# version_1_1.net
KiCad netlist of a schematic drawn in EAGLE
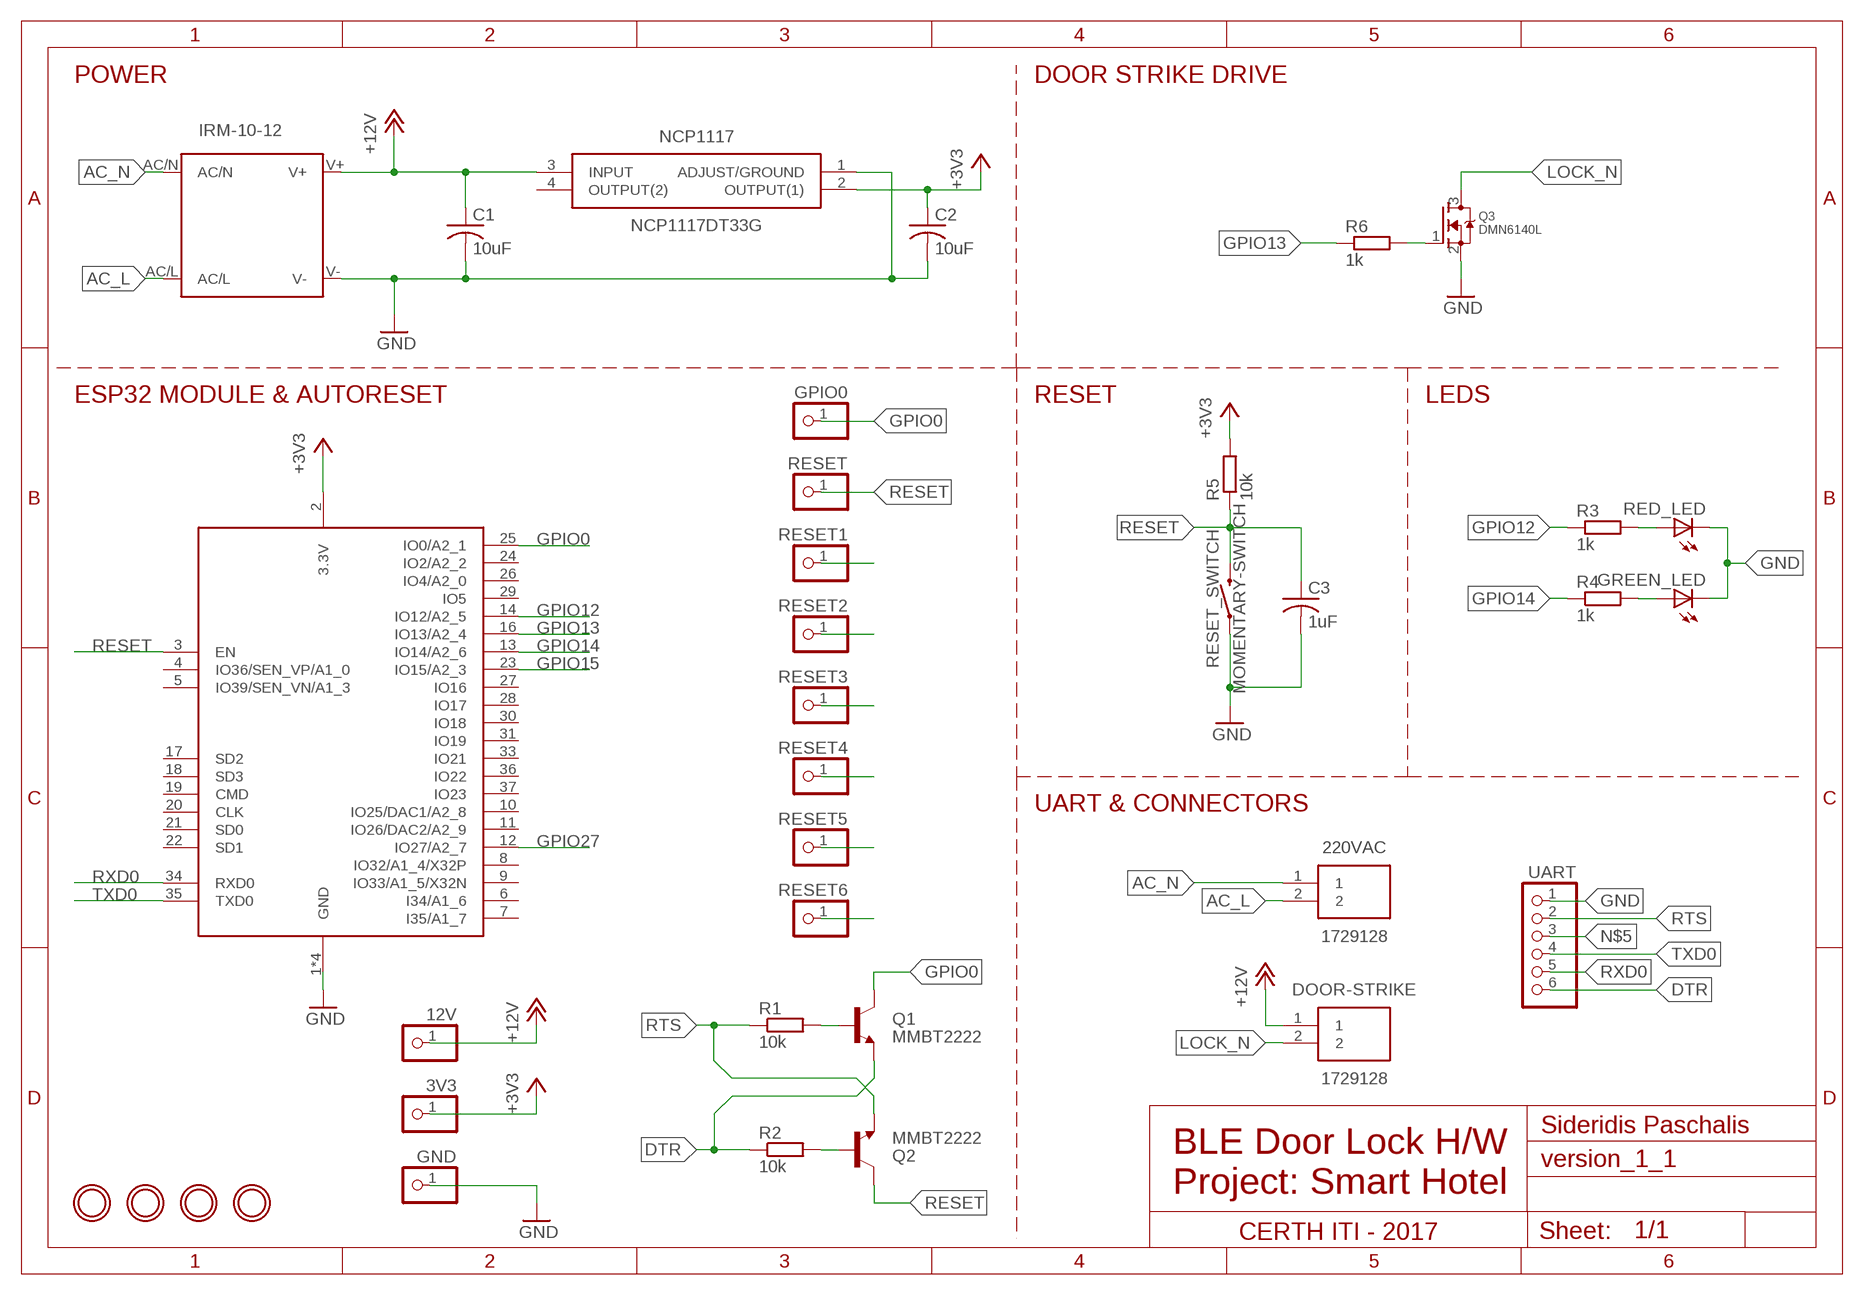
[diagram p0: schematic, sheet 1]

(export (version "E")
  (design (tool "Eeschema 10.0.6"))
  (components
    (comp (ref "3V3")
      (value "PINHD-1X1")
      (footprint "eagle-import:1X01")
      (libsource (lib "eagle-import") (part "PINHD-1X1"))
    )
    (comp (ref "12V")
      (value "PINHD-1X1")
      (footprint "eagle-import:1X01")
      (libsource (lib "eagle-import") (part "PINHD-1X1"))
    )
    (comp (ref "220VAC")
      (value "1729128")
      (footprint "eagle-import:HDRV2W110P0X508_1X2_1016X810X1")
      (fields (field (name "RS_PART_NUMBER") "1930586"))
      (libsource (lib "eagle-import") (part "1729128"))
    )
    (comp (ref "C1")
      (value "10uF")
      (footprint "eagle-import:C0805")
      (libsource (lib "eagle-import") (part "C-USC0805"))
    )
    (comp (ref "C2")
      (value "10uF")
      (footprint "eagle-import:C0805")
      (libsource (lib "eagle-import") (part "C-USC0805"))
    )
    (comp (ref "C3")
      (value "1uF")
      (footprint "eagle-import:C0805")
      (libsource (lib "eagle-import") (part "C-USC0805"))
    )
    (comp (ref "DOOR-STRIKE")
      (value "1729128")
      (footprint "eagle-import:HDRV2W110P0X508_1X2_1016X810X1")
      (fields (field (name "RS_PART_NUMBER") "1930586"))
      (libsource (lib "eagle-import") (part "1729128"))
    )
    (comp (ref "ESP32")
      (value "ESP32_WROOM32_SKINNY")
      (footprint "eagle-import:WROOM32_SKINNY")
      (libsource (lib "eagle-import") (part "ESP32_WROOM32_SKINNY"))
    )
    (comp (ref "GND")
      (value "PINHD-1X1")
      (footprint "eagle-import:1X01")
      (libsource (lib "eagle-import") (part "PINHD-1X1"))
    )
    (comp (ref "GPIO0")
      (value "PINHD-1X1")
      (footprint "eagle-import:1X01")
      (libsource (lib "eagle-import") (part "PINHD-1X1"))
    )
    (comp (ref "GREEN_LED")
      (value "LED5MM")
      (footprint "eagle-import:LED5MM")
      (libsource (lib "eagle-import") (part "LED5MM"))
    )
    (comp (ref "IRM-10-12")
      (value "IRM_05/10")
      (footprint "eagle-import:IRM_05_10")
      (libsource (lib "eagle-import") (part "IRM_05/10"))
    )
    (comp (ref "NCP1117")
      (value "NCP1117DT33G")
      (footprint "eagle-import:TO229P990X238-4N")
      (fields (field (name "RS_PART_NUMBER") "1023504"))
      (libsource (lib "eagle-import") (part "NCP1117DT33G"))
    )
    (comp (ref "Q1")
      (value "MMBT2222")
      (footprint "eagle-import:SOT23")
      (libsource (lib "eagle-import") (part "TRANSISTOR_NPNSOT23"))
    )
    (comp (ref "Q2")
      (value "MMBT2222")
      (footprint "eagle-import:SOT23")
      (libsource (lib "eagle-import") (part "TRANSISTOR_NPNSOT23"))
    )
    (comp (ref "Q3")
      (value "DMN6140L")
      (footprint "eagle-import:SOT23")
      (libsource (lib "eagle-import") (part "MOSFET-NREFLOW"))
    )
    (comp (ref "R1")
      (value "10k")
      (footprint "eagle-import:R0805")
      (libsource (lib "eagle-import") (part "R-EU_R0805"))
    )
    (comp (ref "R2")
      (value "10k")
      (footprint "eagle-import:R0805")
      (libsource (lib "eagle-import") (part "R-EU_R0805"))
    )
    (comp (ref "R3")
      (value "1k")
      (footprint "eagle-import:R0805")
      (libsource (lib "eagle-import") (part "R-EU_R0805"))
    )
    (comp (ref "R4")
      (value "1k")
      (footprint "eagle-import:R0805")
      (libsource (lib "eagle-import") (part "R-EU_R0805"))
    )
    (comp (ref "R5")
      (value "10k")
      (footprint "eagle-import:R0805")
      (libsource (lib "eagle-import") (part "R-EU_R0805"))
    )
    (comp (ref "R6")
      (value "1k")
      (footprint "eagle-import:R0805")
      (libsource (lib "eagle-import") (part "R-EU_R0805"))
    )
    (comp (ref "RED_LED")
      (value "LED5MM")
      (footprint "eagle-import:LED5MM")
      (libsource (lib "eagle-import") (part "LED5MM"))
    )
    (comp (ref "RESET")
      (value "PINHD-1X1")
      (footprint "eagle-import:1X01")
      (libsource (lib "eagle-import") (part "PINHD-1X1"))
    )
    (comp (ref "RESET1")
      (value "PINHD-1X1")
      (footprint "eagle-import:1X01")
      (libsource (lib "eagle-import") (part "PINHD-1X1"))
    )
    (comp (ref "RESET2")
      (value "PINHD-1X1")
      (footprint "eagle-import:1X01")
      (libsource (lib "eagle-import") (part "PINHD-1X1"))
    )
    (comp (ref "RESET3")
      (value "PINHD-1X1")
      (footprint "eagle-import:1X01")
      (libsource (lib "eagle-import") (part "PINHD-1X1"))
    )
    (comp (ref "RESET4")
      (value "PINHD-1X1")
      (footprint "eagle-import:1X01")
      (libsource (lib "eagle-import") (part "PINHD-1X1"))
    )
    (comp (ref "RESET5")
      (value "PINHD-1X1")
      (footprint "eagle-import:1X01")
      (libsource (lib "eagle-import") (part "PINHD-1X1"))
    )
    (comp (ref "RESET6")
      (value "PINHD-1X1")
      (footprint "eagle-import:1X01")
      (libsource (lib "eagle-import") (part "PINHD-1X1"))
    )
    (comp (ref "RESET_SWITCH")
      (value "MOMENTARY-SWITCH")
      (footprint "eagle-import:TACTILE_SWITCH_SMD_6.2MM_TALL")
      (libsource (lib "eagle-import") (part "MOMENTARY-SWITCH-SPST-SMD-6.2MM-TALL"))
    )
    (comp (ref "U$1")
      (value "MOUNTINGHOLE2.5")
      (footprint "eagle-import:MOUNTINGHOLE_2.5_PLATED")
      (libsource (lib "eagle-import") (part "MOUNTINGHOLE2.5"))
    )
    (comp (ref "U$2")
      (value "MOUNTINGHOLE2.5")
      (footprint "eagle-import:MOUNTINGHOLE_2.5_PLATED")
      (libsource (lib "eagle-import") (part "MOUNTINGHOLE2.5"))
    )
    (comp (ref "U$3")
      (value "MOUNTINGHOLE2.5")
      (footprint "eagle-import:MOUNTINGHOLE_2.5_PLATED")
      (libsource (lib "eagle-import") (part "MOUNTINGHOLE2.5"))
    )
    (comp (ref "U$4")
      (value "MOUNTINGHOLE2.5")
      (footprint "eagle-import:MOUNTINGHOLE_2.5_PLATED")
      (libsource (lib "eagle-import") (part "MOUNTINGHOLE2.5"))
    )
    (comp (ref "UART")
      (value "PINHD-1X6")
      (footprint "eagle-import:1X06")
      (libsource (lib "eagle-import") (part "PINHD-1X6"))
    )
  )
  (nets
    (net (code "1") (name "+3V3") (class "Default")
      (node (ref "3V3") (pin "1") (pinfunction "1_1") (pintype "passive"))
      (node (ref "C2") (pin "1") (pinfunction "1_1") (pintype "passive"))
      (node (ref "ESP32") (pin "2") (pinfunction "3.3V_2") (pintype "passive"))
      (node (ref "NCP1117") (pin "2") (pinfunction "OUTPUT(1)_2") (pintype "output"))
      (node (ref "R5") (pin "2") (pinfunction "2_2") (pintype "passive"))
    )
    (net (code "2") (name "+12V") (class "Default")
      (node (ref "12V") (pin "1") (pinfunction "1_1") (pintype "passive"))
      (node (ref "C1") (pin "1") (pinfunction "1_1") (pintype "passive"))
      (node (ref "DOOR-STRIKE") (pin "1") (pinfunction "1_1") (pintype "passive"))
      (node (ref "IRM-10-12") (pin "V+") (pinfunction "V+_V+") (pintype "output"))
      (node (ref "NCP1117") (pin "3") (pinfunction "INPUT_3") (pintype "input"))
    )
    (net (code "3") (name "/GPIO15") (class "Default")
      (node (ref "ESP32") (pin "23") (pinfunction "IO15/A2_3_23") (pintype "bidirectional"))
    )
    (net (code "4") (name "/GPIO27") (class "Default")
      (node (ref "ESP32") (pin "12") (pinfunction "IO27/A2_7_12") (pintype "bidirectional"))
    )
    (net (code "5") (name "AC_L") (class "Default")
      (node (ref "220VAC") (pin "2") (pinfunction "2_2") (pintype "passive"))
      (node (ref "IRM-10-12") (pin "AC/L") (pinfunction "AC/L_AC/L") (pintype "input"))
    )
    (net (code "6") (name "AC_N") (class "Default")
      (node (ref "220VAC") (pin "1") (pinfunction "1_1") (pintype "passive"))
      (node (ref "IRM-10-12") (pin "AC/N") (pinfunction "AC/N_AC/N") (pintype "input"))
    )
    (net (code "7") (name "DTR") (class "Default")
      (node (ref "Q1") (pin "2") (pinfunction "E_2") (pintype "passive"))
      (node (ref "R2") (pin "1") (pinfunction "1_1") (pintype "passive"))
      (node (ref "UART") (pin "6") (pinfunction "6_6") (pintype "passive"))
    )
    (net (code "8") (name "GND") (class "Default")
      (node (ref "C1") (pin "2") (pinfunction "2_2") (pintype "passive"))
      (node (ref "C2") (pin "2") (pinfunction "2_2") (pintype "passive"))
      (node (ref "C3") (pin "2") (pinfunction "2_2") (pintype "passive"))
      (node (ref "ESP32") (pin "1") (pinfunction "GND_1") (pintype "passive"))
      (node (ref "ESP32") (pin "15") (pinfunction "GND_15") (pintype "passive"))
      (node (ref "ESP32") (pin "38") (pinfunction "GND_38") (pintype "passive"))
      (node (ref "ESP32") (pin "P$1") (pinfunction "GND_P$1") (pintype "passive"))
      (node (ref "GND") (pin "1") (pinfunction "1_1") (pintype "passive"))
      (node (ref "GREEN_LED") (pin "K") (pinfunction "C_K") (pintype "passive"))
      (node (ref "IRM-10-12") (pin "V-") (pinfunction "V-_V-") (pintype "output"))
      (node (ref "NCP1117") (pin "1") (pinfunction "ADJUST/GROUND_1") (pintype "passive"))
      (node (ref "Q3") (pin "2") (pinfunction "S_2") (pintype "bidirectional"))
      (node (ref "RED_LED") (pin "K") (pinfunction "C_K") (pintype "passive"))
      (node (ref "RESET_SWITCH") (pin "A2") (pinfunction "1_A2") (pintype "passive"))
      (node (ref "UART") (pin "1") (pinfunction "1_1") (pintype "passive"))
    )
    (net (code "9") (name "GPIO0") (class "Default")
      (node (ref "ESP32") (pin "25") (pinfunction "IO0/A2_1_25") (pintype "bidirectional"))
      (node (ref "GPIO0") (pin "1") (pinfunction "1_1") (pintype "passive"))
      (node (ref "Q1") (pin "3") (pinfunction "C_3") (pintype "passive"))
    )
    (net (code "10") (name "GPIO12") (class "Default")
      (node (ref "ESP32") (pin "14") (pinfunction "IO12/A2_5_14") (pintype "bidirectional"))
      (node (ref "R3") (pin "1") (pinfunction "1_1") (pintype "passive"))
    )
    (net (code "11") (name "GPIO13") (class "Default")
      (node (ref "ESP32") (pin "16") (pinfunction "IO13/A2_4_16") (pintype "bidirectional"))
      (node (ref "R6") (pin "1") (pinfunction "1_1") (pintype "passive"))
    )
    (net (code "12") (name "GPIO14") (class "Default")
      (node (ref "ESP32") (pin "13") (pinfunction "IO14/A2_6_13") (pintype "bidirectional"))
      (node (ref "R4") (pin "1") (pinfunction "1_1") (pintype "passive"))
    )
    (net (code "13") (name "LOCK_N") (class "Default")
      (node (ref "DOOR-STRIKE") (pin "2") (pinfunction "2_2") (pintype "passive"))
      (node (ref "Q3") (pin "3") (pinfunction "D_3") (pintype "bidirectional"))
    )
    (net (code "14") (name "N$5") (class "Default")
      (node (ref "UART") (pin "3") (pinfunction "3_3") (pintype "passive"))
    )
    (net (code "15") (name "Net-(GREEN_LED-PadA)") (class "Default")
      (node (ref "GREEN_LED") (pin "A") (pinfunction "A_A") (pintype "passive"))
      (node (ref "R4") (pin "2") (pinfunction "2_2") (pintype "passive"))
    )
    (net (code "16") (name "Net-(Q1-B)") (class "Default")
      (node (ref "Q1") (pin "1") (pinfunction "B_1") (pintype "passive"))
      (node (ref "R1") (pin "2") (pinfunction "2_2") (pintype "passive"))
    )
    (net (code "17") (name "Net-(Q2-B)") (class "Default")
      (node (ref "Q2") (pin "1") (pinfunction "B_1") (pintype "passive"))
      (node (ref "R2") (pin "2") (pinfunction "2_2") (pintype "passive"))
    )
    (net (code "18") (name "Net-(Q3-G)") (class "Default")
      (node (ref "Q3") (pin "1") (pinfunction "G_1") (pintype "bidirectional"))
      (node (ref "R6") (pin "2") (pinfunction "2_2") (pintype "passive"))
    )
    (net (code "19") (name "Net-(R3-Pad2)") (class "Default")
      (node (ref "R3") (pin "2") (pinfunction "2_2") (pintype "passive"))
      (node (ref "RED_LED") (pin "A") (pinfunction "A_A") (pintype "passive"))
    )
    (net (code "20") (name "RESET") (class "Default")
      (node (ref "C3") (pin "1") (pinfunction "1_1") (pintype "passive"))
      (node (ref "ESP32") (pin "3") (pinfunction "EN_3") (pintype "input"))
      (node (ref "Q2") (pin "3") (pinfunction "C_3") (pintype "passive"))
      (node (ref "R5") (pin "1") (pinfunction "1_1") (pintype "passive"))
      (node (ref "RESET") (pin "1") (pinfunction "1_1") (pintype "passive"))
      (node (ref "RESET_SWITCH") (pin "B2") (pinfunction "2_B2") (pintype "passive"))
    )
    (net (code "21") (name "RTS") (class "Default")
      (node (ref "Q2") (pin "2") (pinfunction "E_2") (pintype "passive"))
      (node (ref "R1") (pin "1") (pinfunction "1_1") (pintype "passive"))
      (node (ref "UART") (pin "2") (pinfunction "2_2") (pintype "passive"))
    )
    (net (code "22") (name "RXD0") (class "Default")
      (node (ref "ESP32") (pin "34") (pinfunction "RXD0_34") (pintype "input"))
      (node (ref "UART") (pin "5") (pinfunction "5_5") (pintype "passive"))
    )
    (net (code "23") (name "TXD0") (class "Default")
      (node (ref "ESP32") (pin "35") (pinfunction "TXD0_35") (pintype "output"))
      (node (ref "UART") (pin "4") (pinfunction "4_4") (pintype "passive"))
    )
    (net (code "24") (name "unconnected-(ESP32-CLK-Pad20)") (class "Default")
      (node (ref "ESP32") (pin "20") (pinfunction "CLK_20") (pintype "bidirectional"))
    )
    (net (code "25") (name "unconnected-(ESP32-CMD-Pad19)") (class "Default")
      (node (ref "ESP32") (pin "19") (pinfunction "CMD_19") (pintype "bidirectional"))
    )
    (net (code "26") (name "unconnected-(ESP32-I34{slash}A1_6-Pad6)") (class "Default")
      (node (ref "ESP32") (pin "6") (pinfunction "I34/A1_6_6") (pintype "bidirectional"))
    )
    (net (code "27") (name "unconnected-(ESP32-I35{slash}A1_7-Pad7)") (class "Default")
      (node (ref "ESP32") (pin "7") (pinfunction "I35/A1_7_7") (pintype "bidirectional"))
    )
    (net (code "28") (name "unconnected-(ESP32-IO2{slash}A2_2-Pad24)") (class "Default")
      (node (ref "ESP32") (pin "24") (pinfunction "IO2/A2_2_24") (pintype "bidirectional"))
    )
    (net (code "29") (name "unconnected-(ESP32-IO4{slash}A2_0-Pad26)") (class "Default")
      (node (ref "ESP32") (pin "26") (pinfunction "IO4/A2_0_26") (pintype "bidirectional"))
    )
    (net (code "30") (name "unconnected-(ESP32-IO5-Pad29)") (class "Default")
      (node (ref "ESP32") (pin "29") (pinfunction "IO5_29") (pintype "bidirectional"))
    )
    (net (code "31") (name "unconnected-(ESP32-IO16-Pad27)") (class "Default")
      (node (ref "ESP32") (pin "27") (pinfunction "IO16_27") (pintype "bidirectional"))
    )
    (net (code "32") (name "unconnected-(ESP32-IO17-Pad28)") (class "Default")
      (node (ref "ESP32") (pin "28") (pinfunction "IO17_28") (pintype "bidirectional"))
    )
    (net (code "33") (name "unconnected-(ESP32-IO18-Pad30)") (class "Default")
      (node (ref "ESP32") (pin "30") (pinfunction "IO18_30") (pintype "bidirectional"))
    )
    (net (code "34") (name "unconnected-(ESP32-IO19-Pad31)") (class "Default")
      (node (ref "ESP32") (pin "31") (pinfunction "IO19_31") (pintype "bidirectional"))
    )
    (net (code "35") (name "unconnected-(ESP32-IO21-Pad33)") (class "Default")
      (node (ref "ESP32") (pin "33") (pinfunction "IO21_33") (pintype "bidirectional"))
    )
    (net (code "36") (name "unconnected-(ESP32-IO22-Pad36)") (class "Default")
      (node (ref "ESP32") (pin "36") (pinfunction "IO22_36") (pintype "bidirectional"))
    )
    (net (code "37") (name "unconnected-(ESP32-IO23-Pad37)") (class "Default")
      (node (ref "ESP32") (pin "37") (pinfunction "IO23_37") (pintype "bidirectional"))
    )
    (net (code "38") (name "unconnected-(ESP32-IO25{slash}DAC1{slash}A2_8-Pad10)") (class "Default")
      (node (ref "ESP32") (pin "10") (pinfunction "IO25/DAC1/A2_8_10") (pintype "bidirectional"))
    )
    (net (code "39") (name "unconnected-(ESP32-IO26{slash}DAC2{slash}A2_9-Pad11)") (class "Default")
      (node (ref "ESP32") (pin "11") (pinfunction "IO26/DAC2/A2_9_11") (pintype "bidirectional"))
    )
    (net (code "40") (name "unconnected-(ESP32-IO32{slash}A1_4{slash}X32P-Pad8)") (class "Default")
      (node (ref "ESP32") (pin "8") (pinfunction "IO32/A1_4/X32P_8") (pintype "bidirectional"))
    )
    (net (code "41") (name "unconnected-(ESP32-IO33{slash}A1_5{slash}X32N-Pad9)") (class "Default")
      (node (ref "ESP32") (pin "9") (pinfunction "IO33/A1_5/X32N_9") (pintype "bidirectional"))
    )
    (net (code "42") (name "unconnected-(ESP32-IO36{slash}SEN_VP{slash}A1_0-Pad4)") (class "Default")
      (node (ref "ESP32") (pin "4") (pinfunction "IO36/SEN_VP/A1_0_4") (pintype "passive"))
    )
    (net (code "43") (name "unconnected-(ESP32-IO39{slash}SEN_VN{slash}A1_3-Pad5)") (class "Default")
      (node (ref "ESP32") (pin "5") (pinfunction "IO39/SEN_VN/A1_3_5") (pintype "passive"))
    )
    (net (code "44") (name "unconnected-(ESP32-SD0-Pad21)") (class "Default")
      (node (ref "ESP32") (pin "21") (pinfunction "SD0_21") (pintype "bidirectional"))
    )
    (net (code "45") (name "unconnected-(ESP32-SD1-Pad22)") (class "Default")
      (node (ref "ESP32") (pin "22") (pinfunction "SD1_22") (pintype "bidirectional"))
    )
    (net (code "46") (name "unconnected-(ESP32-SD2-Pad17)") (class "Default")
      (node (ref "ESP32") (pin "17") (pinfunction "SD2_17") (pintype "bidirectional"))
    )
    (net (code "47") (name "unconnected-(ESP32-SD3-Pad18)") (class "Default")
      (node (ref "ESP32") (pin "18") (pinfunction "SD3_18") (pintype "bidirectional"))
    )
    (net (code "48") (name "unconnected-(NCP1117-OUTPUT(2)-Pad4)") (class "Default")
      (node (ref "NCP1117") (pin "4") (pinfunction "OUTPUT(2)_4") (pintype "output"))
    )
    (net (code "49") (name "unconnected-(RESET1-Pad1)") (class "Default")
      (node (ref "RESET1") (pin "1") (pinfunction "1_1") (pintype "passive"))
    )
    (net (code "50") (name "unconnected-(RESET2-Pad1)") (class "Default")
      (node (ref "RESET2") (pin "1") (pinfunction "1_1") (pintype "passive"))
    )
    (net (code "51") (name "unconnected-(RESET3-Pad1)") (class "Default")
      (node (ref "RESET3") (pin "1") (pinfunction "1_1") (pintype "passive"))
    )
    (net (code "52") (name "unconnected-(RESET4-Pad1)") (class "Default")
      (node (ref "RESET4") (pin "1") (pinfunction "1_1") (pintype "passive"))
    )
    (net (code "53") (name "unconnected-(RESET5-Pad1)") (class "Default")
      (node (ref "RESET5") (pin "1") (pinfunction "1_1") (pintype "passive"))
    )
    (net (code "54") (name "unconnected-(RESET6-Pad1)") (class "Default")
      (node (ref "RESET6") (pin "1") (pinfunction "1_1") (pintype "passive"))
    )
  )
)
